# esp32-Prototipo_Roger.net
KiCad netlist of a schematic drawn in EAGLE
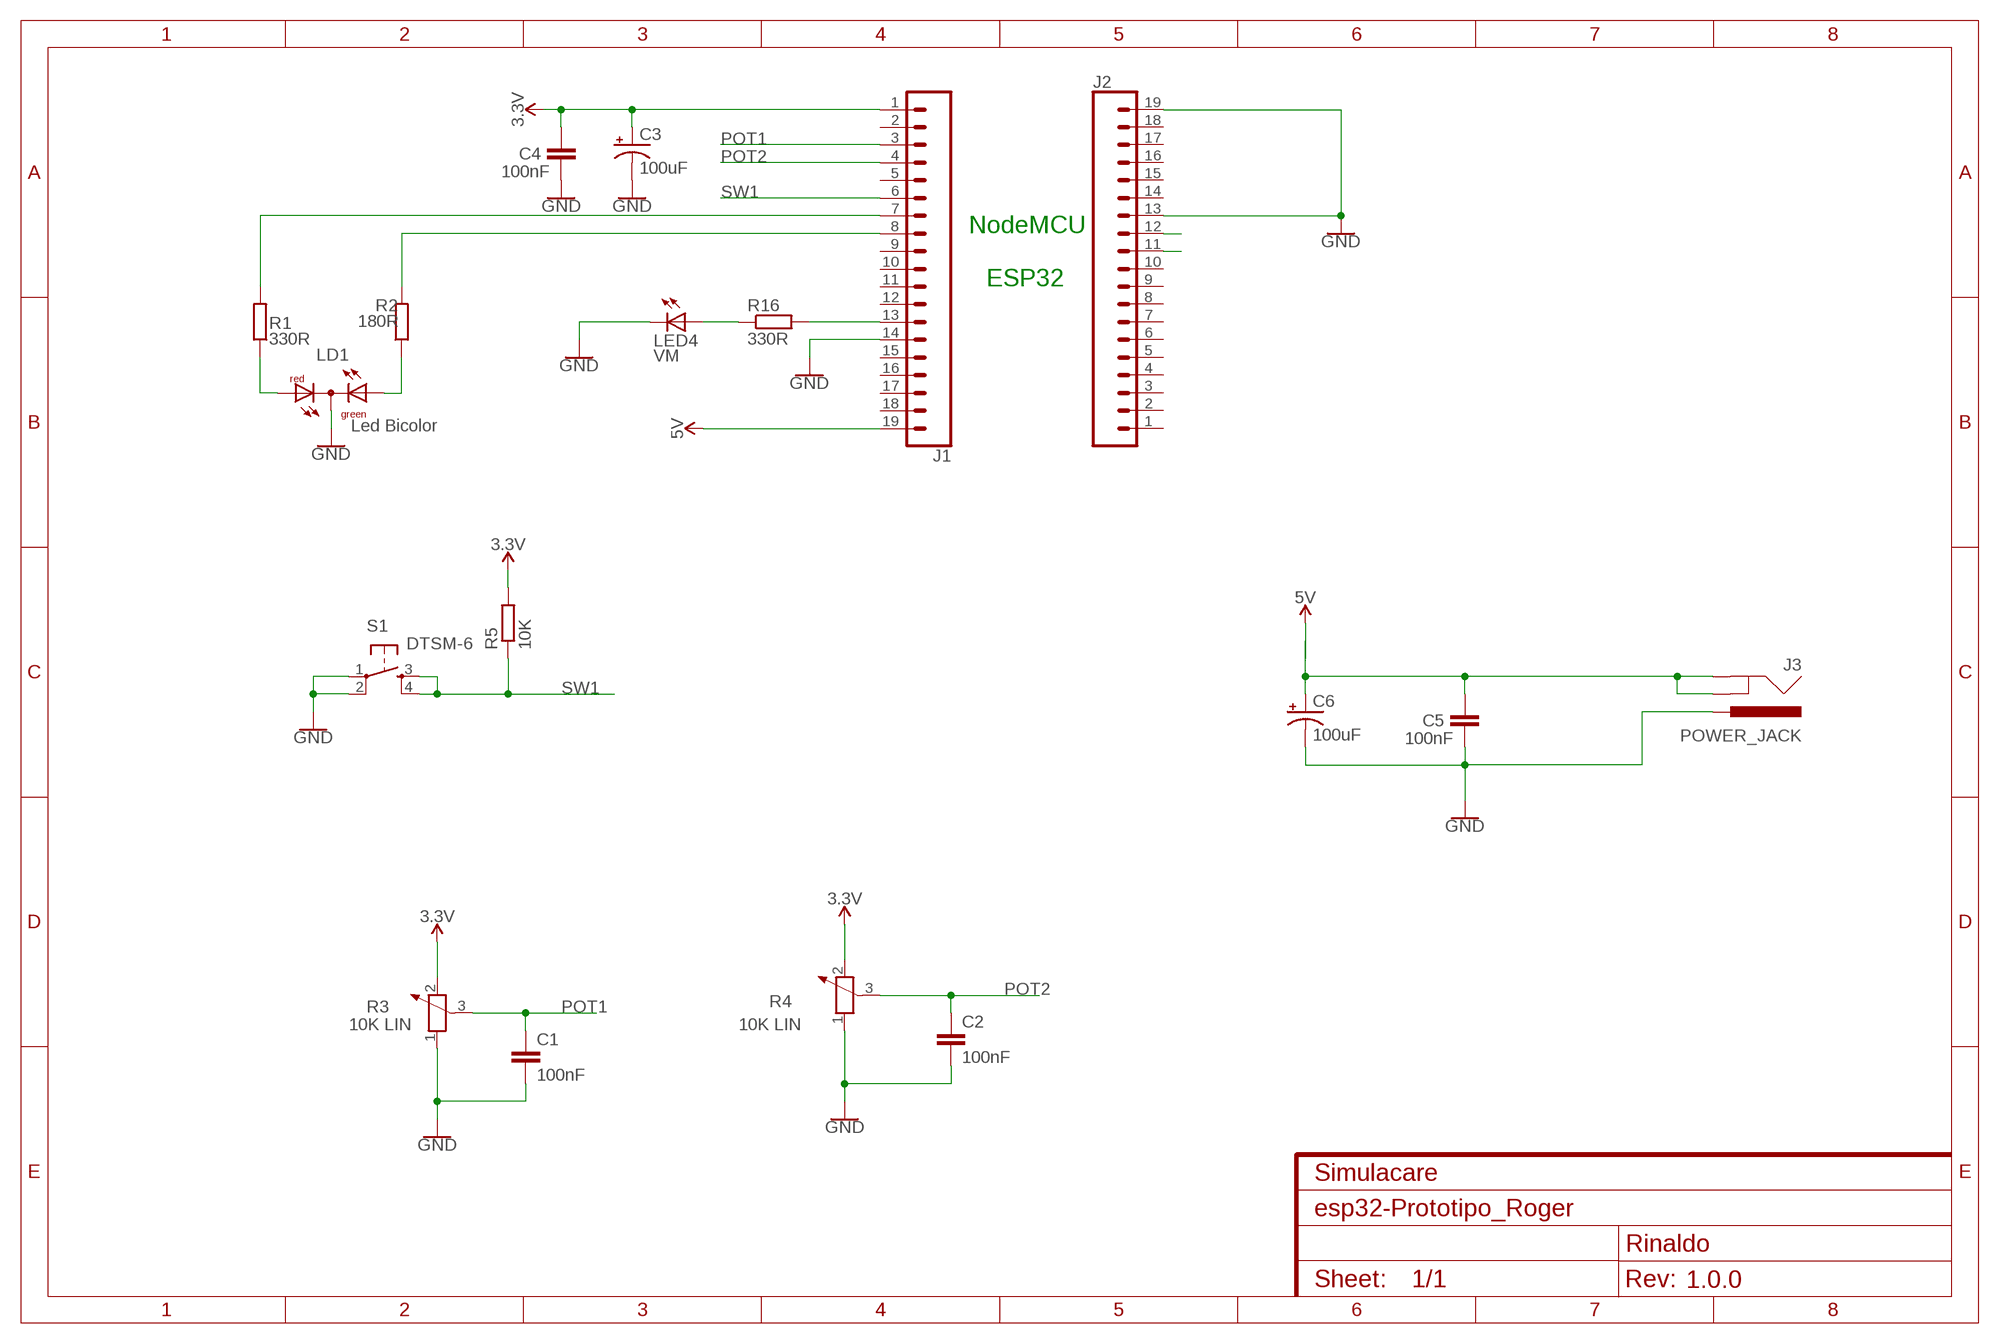
[diagram p0: schematic, sheet 1]

(export (version "E")
  (design (tool "Eeschema 10.0.6"))
  (components
    (comp (ref "C1")
      (value "100nF")
      (footprint "eagle-import:C025-024X044")
      (libsource (lib "eagle-import") (part "C-EU025-024X044"))
    )
    (comp (ref "C2")
      (value "100nF")
      (footprint "eagle-import:C025-024X044")
      (libsource (lib "eagle-import") (part "C-EU025-024X044"))
    )
    (comp (ref "C3")
      (value "100uF")
      (footprint "eagle-import:085CS_1AR")
      (libsource (lib "eagle-import") (part "CPOL-US085CS-1AR"))
    )
    (comp (ref "C4")
      (value "100nF")
      (footprint "eagle-import:C025-024X044")
      (libsource (lib "eagle-import") (part "resistor_348_C-EU025-024X044"))
    )
    (comp (ref "C5")
      (value "100nF")
      (footprint "eagle-import:C025-024X044")
      (libsource (lib "eagle-import") (part "resistor_348_C-EU025-024X044"))
    )
    (comp (ref "C6")
      (value "100uF")
      (footprint "eagle-import:085CS_1AR")
      (libsource (lib "eagle-import") (part "CPOL-US085CS-1AR"))
    )
    (comp (ref "J1")
      (value "CONN_19")
      (footprint "eagle-import:1X19")
      (libsource (lib "eagle-import") (part "CONN_19"))
    )
    (comp (ref "J2")
      (value "CONN_19")
      (footprint "eagle-import:1X19")
      (libsource (lib "eagle-import") (part "CONN_19"))
    )
    (comp (ref "J3")
      (value "POWER_JACK")
      (footprint "eagle-import:POWER_JACK_PTH")
      (libsource (lib "eagle-import") (part "POWER_JACK"))
    )
    (comp (ref "LD1")
      (value "Led Bicolor")
      (footprint "eagle-import:DUOLED-C-5MM")
      (libsource (lib "eagle-import") (part "DUOLED-RG-C"))
    )
    (comp (ref "LED4")
      (value "VM")
      (footprint "eagle-import:LED5MM")
      (libsource (lib "eagle-import") (part "LED5MM"))
    )
    (comp (ref "R1")
      (value "330R")
      (footprint "eagle-import:R0603")
      (libsource (lib "eagle-import") (part "R-EU_R0603"))
    )
    (comp (ref "R2")
      (value "180R")
      (footprint "eagle-import:R0603")
      (libsource (lib "eagle-import") (part "R-EU_R0603"))
    )
    (comp (ref "R3")
      (value "10K LIN")
      (footprint "eagle-import:PT-10")
      (libsource (lib "eagle-import") (part "POTENTIOMETER_PT-10"))
    )
    (comp (ref "R4")
      (value "10K LIN")
      (footprint "eagle-import:PT-10")
      (libsource (lib "eagle-import") (part "POTENTIOMETER_PT-10"))
    )
    (comp (ref "R5")
      (value "10K")
      (footprint "eagle-import:R0603")
      (libsource (lib "eagle-import") (part "R-EU_R0603"))
    )
    (comp (ref "R16")
      (value "330R")
      (footprint "eagle-import:R0603")
      (libsource (lib "eagle-import") (part "R-EU_R0603"))
    )
    (comp (ref "S1")
      (value "DTSM-6")
      (footprint "eagle-import:DTSM-6")
      (libsource (lib "eagle-import") (part "DTSM-6"))
    )
  )
  (nets
    (net (code "1") (name "/POT1") (class "Default")
      (node (ref "C1") (pin "1") (pinfunction "1_1") (pintype "passive"))
      (node (ref "J1") (pin "3") (pinfunction "3_3") (pintype "passive"))
      (node (ref "R3") (pin "3") (pinfunction "3_3") (pintype "passive"))
    )
    (net (code "2") (name "/POT2") (class "Default")
      (node (ref "C2") (pin "1") (pinfunction "1_1") (pintype "passive"))
      (node (ref "J1") (pin "4") (pinfunction "4_4") (pintype "passive"))
      (node (ref "R4") (pin "3") (pinfunction "3_3") (pintype "passive"))
    )
    (net (code "3") (name "/SW1") (class "Default")
      (node (ref "J1") (pin "6") (pinfunction "6_6") (pintype "passive"))
      (node (ref "R5") (pin "1") (pinfunction "1_1") (pintype "passive"))
      (node (ref "S1") (pin "3") (pinfunction "3_3") (pintype "passive"))
      (node (ref "S1") (pin "4") (pinfunction "4_4") (pintype "passive"))
    )
    (net (code "4") (name "3.3V") (class "Default")
      (node (ref "C3") (pin "+") (pinfunction "+_+") (pintype "passive"))
      (node (ref "C4") (pin "1") (pinfunction "1_1") (pintype "passive"))
      (node (ref "J1") (pin "1") (pinfunction "1_1") (pintype "passive"))
      (node (ref "R3") (pin "2") (pinfunction "2_2") (pintype "passive"))
      (node (ref "R4") (pin "2") (pinfunction "2_2") (pintype "passive"))
      (node (ref "R5") (pin "2") (pinfunction "2_2") (pintype "passive"))
    )
    (net (code "5") (name "5V") (class "Default")
      (node (ref "J1") (pin "19") (pinfunction "19_19") (pintype "passive"))
    )
    (net (code "6") (name "GND") (class "Default")
      (node (ref "C1") (pin "2") (pinfunction "2_2") (pintype "passive"))
      (node (ref "C2") (pin "2") (pinfunction "2_2") (pintype "passive"))
      (node (ref "C3") (pin "-") (pinfunction "-_-") (pintype "passive"))
      (node (ref "C4") (pin "2") (pinfunction "2_2") (pintype "passive"))
      (node (ref "C5") (pin "2") (pinfunction "2_2") (pintype "passive"))
      (node (ref "C6") (pin "-") (pinfunction "-_-") (pintype "passive"))
      (node (ref "J1") (pin "14") (pinfunction "14_14") (pintype "passive"))
      (node (ref "J2") (pin "13") (pinfunction "13_13") (pintype "passive"))
      (node (ref "J2") (pin "19") (pinfunction "19_19") (pintype "passive"))
      (node (ref "J3") (pin "PWR") (pinfunction "PWR_PWR") (pintype "bidirectional"))
      (node (ref "LD1") (pin "C") (pinfunction "C_C") (pintype "passive"))
      (node (ref "LED4") (pin "K") (pinfunction "C_K") (pintype "passive"))
      (node (ref "R3") (pin "1") (pinfunction "1_1") (pintype "passive"))
      (node (ref "R4") (pin "1") (pinfunction "1_1") (pintype "passive"))
      (node (ref "S1") (pin "1") (pinfunction "1_1") (pintype "passive"))
      (node (ref "S1") (pin "2") (pinfunction "2_2") (pintype "passive"))
    )
    (net (code "7") (name "Net-(C5-Pad1)") (class "Default")
      (node (ref "C5") (pin "1") (pinfunction "1_1") (pintype "passive"))
      (node (ref "C6") (pin "+") (pinfunction "+_+") (pintype "passive"))
      (node (ref "J3") (pin "GND") (pinfunction "GND_GND") (pintype "bidirectional"))
      (node (ref "J3") (pin "GNDBREAK") (pinfunction "GNDBREAK_GNDBREAK") (pintype "bidirectional"))
    )
    (net (code "8") (name "Net-(J1-Pad7)") (class "Default")
      (node (ref "J1") (pin "7") (pinfunction "7_7") (pintype "passive"))
      (node (ref "R1") (pin "2") (pinfunction "2_2") (pintype "passive"))
    )
    (net (code "9") (name "Net-(J1-Pad8)") (class "Default")
      (node (ref "J1") (pin "8") (pinfunction "8_8") (pintype "passive"))
      (node (ref "R2") (pin "2") (pinfunction "2_2") (pintype "passive"))
    )
    (net (code "10") (name "Net-(J1-Pad13)") (class "Default")
      (node (ref "J1") (pin "13") (pinfunction "13_13") (pintype "passive"))
      (node (ref "R16") (pin "2") (pinfunction "2_2") (pintype "passive"))
    )
    (net (code "11") (name "Net-(LD1-AG)") (class "Default")
      (node (ref "LD1") (pin "AX") (pinfunction "AG_AX") (pintype "passive"))
      (node (ref "R2") (pin "1") (pinfunction "1_1") (pintype "passive"))
    )
    (net (code "12") (name "Net-(LD1-PadAR)") (class "Default")
      (node (ref "LD1") (pin "AR") (pinfunction "AR_AR") (pintype "passive"))
      (node (ref "R1") (pin "1") (pinfunction "1_1") (pintype "passive"))
    )
    (net (code "13") (name "Net-(LED4-PadA)") (class "Default")
      (node (ref "LED4") (pin "A") (pinfunction "A_A") (pintype "passive"))
      (node (ref "R16") (pin "1") (pinfunction "1_1") (pintype "passive"))
    )
    (net (code "14") (name "unconnected-(J1-Pad2)") (class "Default")
      (node (ref "J1") (pin "2") (pinfunction "2_2") (pintype "passive"))
    )
    (net (code "15") (name "unconnected-(J1-Pad5)") (class "Default")
      (node (ref "J1") (pin "5") (pinfunction "5_5") (pintype "passive"))
    )
    (net (code "16") (name "unconnected-(J1-Pad9)") (class "Default")
      (node (ref "J1") (pin "9") (pinfunction "9_9") (pintype "passive"))
    )
    (net (code "17") (name "unconnected-(J1-Pad10)") (class "Default")
      (node (ref "J1") (pin "10") (pinfunction "10_10") (pintype "passive"))
    )
    (net (code "18") (name "unconnected-(J1-Pad11)") (class "Default")
      (node (ref "J1") (pin "11") (pinfunction "11_11") (pintype "passive"))
    )
    (net (code "19") (name "unconnected-(J1-Pad12)") (class "Default")
      (node (ref "J1") (pin "12") (pinfunction "12_12") (pintype "passive"))
    )
    (net (code "20") (name "unconnected-(J1-Pad15)") (class "Default")
      (node (ref "J1") (pin "15") (pinfunction "15_15") (pintype "passive"))
    )
    (net (code "21") (name "unconnected-(J1-Pad16)") (class "Default")
      (node (ref "J1") (pin "16") (pinfunction "16_16") (pintype "passive"))
    )
    (net (code "22") (name "unconnected-(J1-Pad17)") (class "Default")
      (node (ref "J1") (pin "17") (pinfunction "17_17") (pintype "passive"))
    )
    (net (code "23") (name "unconnected-(J1-Pad18)") (class "Default")
      (node (ref "J1") (pin "18") (pinfunction "18_18") (pintype "passive"))
    )
    (net (code "24") (name "unconnected-(J2-Pad1)") (class "Default")
      (node (ref "J2") (pin "1") (pinfunction "1_1") (pintype "passive"))
    )
    (net (code "25") (name "unconnected-(J2-Pad2)") (class "Default")
      (node (ref "J2") (pin "2") (pinfunction "2_2") (pintype "passive"))
    )
    (net (code "26") (name "unconnected-(J2-Pad3)") (class "Default")
      (node (ref "J2") (pin "3") (pinfunction "3_3") (pintype "passive"))
    )
    (net (code "27") (name "unconnected-(J2-Pad4)") (class "Default")
      (node (ref "J2") (pin "4") (pinfunction "4_4") (pintype "passive"))
    )
    (net (code "28") (name "unconnected-(J2-Pad5)") (class "Default")
      (node (ref "J2") (pin "5") (pinfunction "5_5") (pintype "passive"))
    )
    (net (code "29") (name "unconnected-(J2-Pad6)") (class "Default")
      (node (ref "J2") (pin "6") (pinfunction "6_6") (pintype "passive"))
    )
    (net (code "30") (name "unconnected-(J2-Pad7)") (class "Default")
      (node (ref "J2") (pin "7") (pinfunction "7_7") (pintype "passive"))
    )
    (net (code "31") (name "unconnected-(J2-Pad8)") (class "Default")
      (node (ref "J2") (pin "8") (pinfunction "8_8") (pintype "passive"))
    )
    (net (code "32") (name "unconnected-(J2-Pad9)") (class "Default")
      (node (ref "J2") (pin "9") (pinfunction "9_9") (pintype "passive"))
    )
    (net (code "33") (name "unconnected-(J2-Pad10)") (class "Default")
      (node (ref "J2") (pin "10") (pinfunction "10_10") (pintype "passive"))
    )
    (net (code "34") (name "unconnected-(J2-Pad11)") (class "Default")
      (node (ref "J2") (pin "11") (pinfunction "11_11") (pintype "passive"))
    )
    (net (code "35") (name "unconnected-(J2-Pad12)") (class "Default")
      (node (ref "J2") (pin "12") (pinfunction "12_12") (pintype "passive"))
    )
    (net (code "36") (name "unconnected-(J2-Pad14)") (class "Default")
      (node (ref "J2") (pin "14") (pinfunction "14_14") (pintype "passive"))
    )
    (net (code "37") (name "unconnected-(J2-Pad15)") (class "Default")
      (node (ref "J2") (pin "15") (pinfunction "15_15") (pintype "passive"))
    )
    (net (code "38") (name "unconnected-(J2-Pad16)") (class "Default")
      (node (ref "J2") (pin "16") (pinfunction "16_16") (pintype "passive"))
    )
    (net (code "39") (name "unconnected-(J2-Pad17)") (class "Default")
      (node (ref "J2") (pin "17") (pinfunction "17_17") (pintype "passive"))
    )
    (net (code "40") (name "unconnected-(J2-Pad18)") (class "Default")
      (node (ref "J2") (pin "18") (pinfunction "18_18") (pintype "passive"))
    )
  )
)
